# FPGA_Supply.net
KiCad netlist of a schematic drawn in Altium Designer
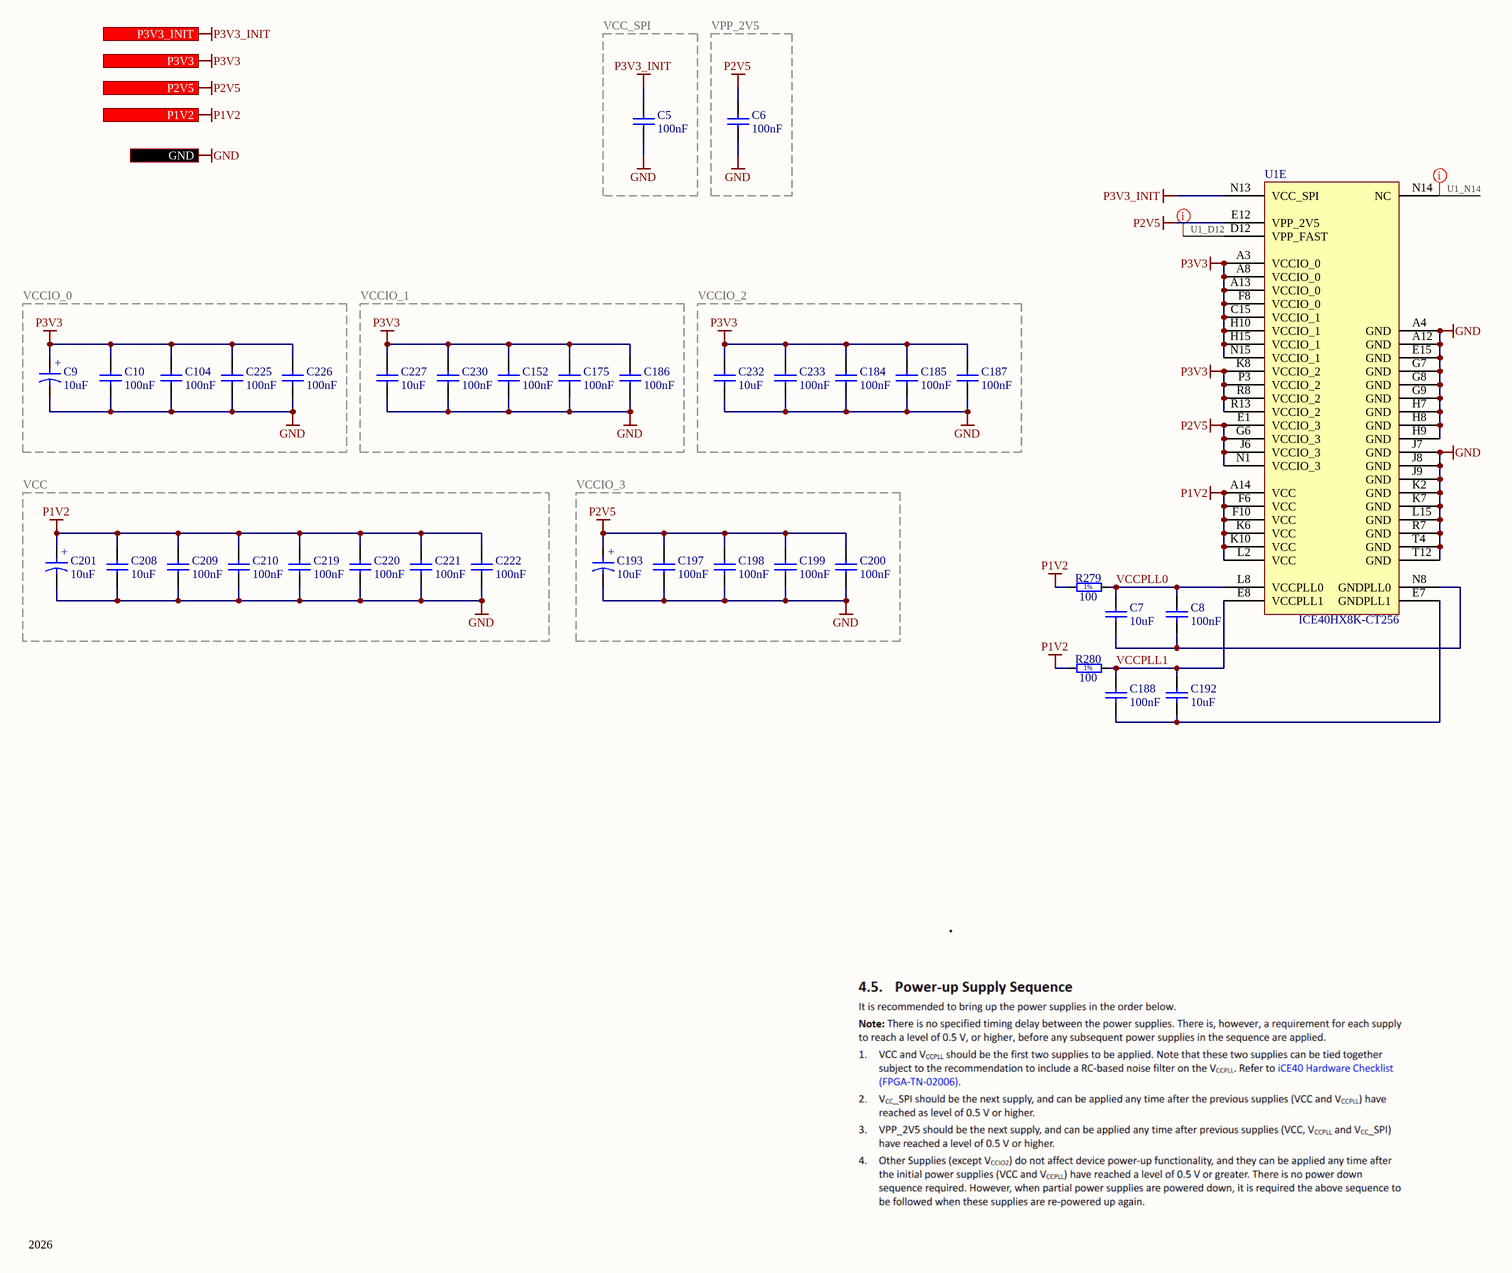
[diagram p0: FPGA_Supply.SchDoc]

(export (version "E")
  (design (tool "Eeschema 10.0.6"))
  (components
    (comp (ref "C5")
      (value "100nF")
      (footprint "CAPC1005X55N")
      (description "Non-polarised capacitor")
      (fields
        (field (name "PART NUMBER") "CC0402_100NF_16V_10%_X5R")
        (field (name "VOLTAGE") "16V")
        (field (name "AUTHOR") "CERN DEM JLC")
      )
      (libsource (lib "Capacitors") (part "Capacitor - non polarized"))
    )
    (comp (ref "C6")
      (value "100nF")
      (footprint "CAPC1005X55N")
      (description "Non-polarised capacitor")
      (fields
        (field (name "PART NUMBER") "CC0402_100NF_16V_10%_X5R")
        (field (name "VOLTAGE") "16V")
        (field (name "AUTHOR") "CERN DEM JLC")
      )
      (libsource (lib "Capacitors") (part "Capacitor - non polarized"))
    )
    (comp (ref "C7")
      (value "10uF")
      (footprint "CAPC1005X70N")
      (description "Non-polarised capacitor")
      (fields
        (field (name "PART NUMBER") "CC0402_10UF_6.3V_20%_X5R")
        (field (name "VOLTAGE") "6.3V")
        (field (name "AUTHOR") "CERN DEM JLC")
      )
      (libsource (lib "Capacitors") (part "Capacitor - non polarized"))
    )
    (comp (ref "C8")
      (value "100nF")
      (footprint "CAPC1005X55N")
      (description "Non-polarised capacitor")
      (fields
        (field (name "PART NUMBER") "CC0402_100NF_16V_10%_X5R")
        (field (name "VOLTAGE") "16V")
        (field (name "AUTHOR") "CERN DEM JLC")
      )
      (libsource (lib "Capacitors") (part "Capacitor - non polarized"))
    )
    (comp (ref "C9")
      (value "10uF")
      (footprint "CAPMP3216X180N")
      (description "Polarised capacitor")
      (fields
        (field (name "PART NUMBER") "CTE3216-18_10UF_16V_20%_AVX_TCJ")
        (field (name "VOLTAGE") "16V")
        (field (name "AUTHOR") "CERN DEM JLC")
      )
      (libsource (lib "Capacitors") (part "Capacitor - polarized"))
    )
    (comp (ref "C10")
      (value "100nF")
      (footprint "CAPC1005X55N")
      (description "Non-polarised capacitor")
      (fields
        (field (name "PART NUMBER") "CC0402_100NF_16V_10%_X5R")
        (field (name "VOLTAGE") "16V")
        (field (name "AUTHOR") "CERN DEM JLC")
      )
      (libsource (lib "Capacitors") (part "Capacitor - non polarized"))
    )
    (comp (ref "C104")
      (value "100nF")
      (footprint "CAPC1005X55N")
      (description "Non-polarised capacitor")
      (fields
        (field (name "PART NUMBER") "CC0402_100NF_16V_10%_X5R")
        (field (name "VOLTAGE") "16V")
        (field (name "AUTHOR") "CERN DEM JLC")
      )
      (libsource (lib "Capacitors") (part "Capacitor - non polarized"))
    )
    (comp (ref "C152")
      (value "100nF")
      (footprint "CAPC1005X55N")
      (description "Non-polarised capacitor")
      (fields
        (field (name "PART NUMBER") "CC0402_100NF_16V_10%_X5R")
        (field (name "VOLTAGE") "16V")
        (field (name "AUTHOR") "CERN DEM JLC")
      )
      (libsource (lib "Capacitors") (part "Capacitor - non polarized"))
    )
    (comp (ref "C175")
      (value "100nF")
      (footprint "CAPC1005X55N")
      (description "Non-polarised capacitor")
      (fields
        (field (name "PART NUMBER") "CC0402_100NF_16V_10%_X5R")
        (field (name "VOLTAGE") "16V")
        (field (name "AUTHOR") "CERN DEM JLC")
      )
      (libsource (lib "Capacitors") (part "Capacitor - non polarized"))
    )
    (comp (ref "C184")
      (value "100nF")
      (footprint "CAPC1005X55N")
      (description "Non-polarised capacitor")
      (fields
        (field (name "PART NUMBER") "CC0402_100NF_16V_10%_X5R")
        (field (name "VOLTAGE") "16V")
        (field (name "AUTHOR") "CERN DEM JLC")
      )
      (libsource (lib "Capacitors") (part "Capacitor - non polarized"))
    )
    (comp (ref "C185")
      (value "100nF")
      (footprint "CAPC1005X55N")
      (description "Non-polarised capacitor")
      (fields
        (field (name "PART NUMBER") "CC0402_100NF_16V_10%_X5R")
        (field (name "VOLTAGE") "16V")
        (field (name "AUTHOR") "CERN DEM JLC")
      )
      (libsource (lib "Capacitors") (part "Capacitor - non polarized"))
    )
    (comp (ref "C186")
      (value "100nF")
      (footprint "CAPC1005X55N")
      (description "Non-polarised capacitor")
      (fields
        (field (name "PART NUMBER") "CC0402_100NF_16V_10%_X5R")
        (field (name "VOLTAGE") "16V")
        (field (name "AUTHOR") "CERN DEM JLC")
      )
      (libsource (lib "Capacitors") (part "Capacitor - non polarized"))
    )
    (comp (ref "C187")
      (value "100nF")
      (footprint "CAPC1005X55N")
      (description "Non-polarised capacitor")
      (fields
        (field (name "PART NUMBER") "CC0402_100NF_16V_10%_X5R")
        (field (name "VOLTAGE") "16V")
        (field (name "AUTHOR") "CERN DEM JLC")
      )
      (libsource (lib "Capacitors") (part "Capacitor - non polarized"))
    )
    (comp (ref "C188")
      (value "100nF")
      (footprint "CAPC1005X55N")
      (description "Non-polarised capacitor")
      (fields
        (field (name "PART NUMBER") "CC0402_100NF_16V_10%_X5R")
        (field (name "VOLTAGE") "16V")
        (field (name "AUTHOR") "CERN DEM JLC")
      )
      (libsource (lib "Capacitors") (part "Capacitor - non polarized"))
    )
    (comp (ref "C192")
      (value "10uF")
      (footprint "CAPC1005X70N")
      (description "Non-polarised capacitor")
      (fields
        (field (name "PART NUMBER") "CC0402_10UF_6.3V_20%_X5R")
        (field (name "VOLTAGE") "6.3V")
        (field (name "AUTHOR") "CERN DEM JLC")
      )
      (libsource (lib "Capacitors") (part "Capacitor - non polarized"))
    )
    (comp (ref "C193")
      (value "10uF")
      (footprint "CAPMP3216X180N")
      (description "Polarised capacitor")
      (fields
        (field (name "PART NUMBER") "CTE3216-18_10UF_16V_20%_AVX_TCJ")
        (field (name "VOLTAGE") "16V")
        (field (name "AUTHOR") "CERN DEM JLC")
      )
      (libsource (lib "Capacitors") (part "Capacitor - polarized"))
    )
    (comp (ref "C197")
      (value "100nF")
      (footprint "CAPC1005X55N")
      (description "Non-polarised capacitor")
      (fields
        (field (name "PART NUMBER") "CC0402_100NF_16V_10%_X5R")
        (field (name "VOLTAGE") "16V")
        (field (name "AUTHOR") "CERN DEM JLC")
      )
      (libsource (lib "Capacitors") (part "Capacitor - non polarized"))
    )
    (comp (ref "C198")
      (value "100nF")
      (footprint "CAPC1005X55N")
      (description "Non-polarised capacitor")
      (fields
        (field (name "PART NUMBER") "CC0402_100NF_16V_10%_X5R")
        (field (name "VOLTAGE") "16V")
        (field (name "AUTHOR") "CERN DEM JLC")
      )
      (libsource (lib "Capacitors") (part "Capacitor - non polarized"))
    )
    (comp (ref "C199")
      (value "100nF")
      (footprint "CAPC1005X55N")
      (description "Non-polarised capacitor")
      (fields
        (field (name "PART NUMBER") "CC0402_100NF_16V_10%_X5R")
        (field (name "VOLTAGE") "16V")
        (field (name "AUTHOR") "CERN DEM JLC")
      )
      (libsource (lib "Capacitors") (part "Capacitor - non polarized"))
    )
    (comp (ref "C200")
      (value "100nF")
      (footprint "CAPC1005X55N")
      (description "Non-polarised capacitor")
      (fields
        (field (name "PART NUMBER") "CC0402_100NF_16V_10%_X5R")
        (field (name "VOLTAGE") "16V")
        (field (name "AUTHOR") "CERN DEM JLC")
      )
      (libsource (lib "Capacitors") (part "Capacitor - non polarized"))
    )
    (comp (ref "C201")
      (value "10uF")
      (footprint "CAPMP3216X180N")
      (description "Polarised capacitor")
      (fields
        (field (name "PART NUMBER") "CTE3216-18_10UF_16V_20%_AVX_TCJ")
        (field (name "VOLTAGE") "16V")
        (field (name "AUTHOR") "CERN DEM JLC")
      )
      (libsource (lib "Capacitors") (part "Capacitor - polarized"))
    )
    (comp (ref "C208")
      (value "10uF")
      (footprint "CAPC2012X135N")
      (description "Non-polarised capacitor")
      (fields
        (field (name "PART NUMBER") "CC0805_10UF_16V_10%_X5R")
        (field (name "VOLTAGE") "16V")
        (field (name "AUTHOR") "CERN DEM JLC")
      )
      (libsource (lib "Capacitors") (part "Capacitor - non polarized"))
    )
    (comp (ref "C209")
      (value "100nF")
      (footprint "CAPC1005X55N")
      (description "Non-polarised capacitor")
      (fields
        (field (name "PART NUMBER") "CC0402_100NF_16V_10%_X5R")
        (field (name "VOLTAGE") "16V")
        (field (name "AUTHOR") "CERN DEM JLC")
      )
      (libsource (lib "Capacitors") (part "Capacitor - non polarized"))
    )
    (comp (ref "C210")
      (value "100nF")
      (footprint "CAPC1005X55N")
      (description "Non-polarised capacitor")
      (fields
        (field (name "PART NUMBER") "CC0402_100NF_16V_10%_X5R")
        (field (name "VOLTAGE") "16V")
        (field (name "AUTHOR") "CERN DEM JLC")
      )
      (libsource (lib "Capacitors") (part "Capacitor - non polarized"))
    )
    (comp (ref "C219")
      (value "100nF")
      (footprint "CAPC1005X55N")
      (description "Non-polarised capacitor")
      (fields
        (field (name "PART NUMBER") "CC0402_100NF_16V_10%_X5R")
        (field (name "VOLTAGE") "16V")
        (field (name "AUTHOR") "CERN DEM JLC")
      )
      (libsource (lib "Capacitors") (part "Capacitor - non polarized"))
    )
    (comp (ref "C220")
      (value "100nF")
      (footprint "CAPC1005X55N")
      (description "Non-polarised capacitor")
      (fields
        (field (name "PART NUMBER") "CC0402_100NF_16V_10%_X5R")
        (field (name "VOLTAGE") "16V")
        (field (name "AUTHOR") "CERN DEM JLC")
      )
      (libsource (lib "Capacitors") (part "Capacitor - non polarized"))
    )
    (comp (ref "C221")
      (value "100nF")
      (footprint "CAPC1005X55N")
      (description "Non-polarised capacitor")
      (fields
        (field (name "PART NUMBER") "CC0402_100NF_16V_10%_X5R")
        (field (name "VOLTAGE") "16V")
        (field (name "AUTHOR") "CERN DEM JLC")
      )
      (libsource (lib "Capacitors") (part "Capacitor - non polarized"))
    )
    (comp (ref "C222")
      (value "100nF")
      (footprint "CAPC1005X55N")
      (description "Non-polarised capacitor")
      (fields
        (field (name "PART NUMBER") "CC0402_100NF_16V_10%_X5R")
        (field (name "VOLTAGE") "16V")
        (field (name "AUTHOR") "CERN DEM JLC")
      )
      (libsource (lib "Capacitors") (part "Capacitor - non polarized"))
    )
    (comp (ref "C225")
      (value "100nF")
      (footprint "CAPC1005X55N")
      (description "Non-polarised capacitor")
      (fields
        (field (name "PART NUMBER") "CC0402_100NF_16V_10%_X5R")
        (field (name "VOLTAGE") "16V")
        (field (name "AUTHOR") "CERN DEM JLC")
      )
      (libsource (lib "Capacitors") (part "Capacitor - non polarized"))
    )
    (comp (ref "C226")
      (value "100nF")
      (footprint "CAPC1005X55N")
      (description "Non-polarised capacitor")
      (fields
        (field (name "PART NUMBER") "CC0402_100NF_16V_10%_X5R")
        (field (name "VOLTAGE") "16V")
        (field (name "AUTHOR") "CERN DEM JLC")
      )
      (libsource (lib "Capacitors") (part "Capacitor - non polarized"))
    )
    (comp (ref "C227")
      (value "10uF")
      (footprint "CAPC2012X135N")
      (description "Non-polarised capacitor")
      (fields
        (field (name "PART NUMBER") "CC0805_10UF_16V_10%_X5R")
        (field (name "VOLTAGE") "16V")
        (field (name "AUTHOR") "CERN DEM JLC")
      )
      (libsource (lib "Capacitors") (part "Capacitor - non polarized"))
    )
    (comp (ref "C230")
      (value "100nF")
      (footprint "CAPC1005X55N")
      (description "Non-polarised capacitor")
      (fields
        (field (name "PART NUMBER") "CC0402_100NF_16V_10%_X5R")
        (field (name "VOLTAGE") "16V")
        (field (name "AUTHOR") "CERN DEM JLC")
      )
      (libsource (lib "Capacitors") (part "Capacitor - non polarized"))
    )
    (comp (ref "C232")
      (value "10uF")
      (footprint "CAPC2012X135N")
      (description "Non-polarised capacitor")
      (fields
        (field (name "PART NUMBER") "CC0805_10UF_16V_10%_X5R")
        (field (name "VOLTAGE") "16V")
        (field (name "AUTHOR") "CERN DEM JLC")
      )
      (libsource (lib "Capacitors") (part "Capacitor - non polarized"))
    )
    (comp (ref "C233")
      (value "100nF")
      (footprint "CAPC1005X55N")
      (description "Non-polarised capacitor")
      (fields
        (field (name "PART NUMBER") "CC0402_100NF_16V_10%_X5R")
        (field (name "VOLTAGE") "16V")
        (field (name "AUTHOR") "CERN DEM JLC")
      )
      (libsource (lib "Capacitors") (part "Capacitor - non polarized"))
    )
    (comp (ref "R279")
      (value "100")
      (footprint "RESC1005X40N")
      (description "Resistor - 1%")
      (fields
        (field (name "PART NUMBER") "R0402_100R_1%_0.0625W_100PPM")
        (field (name "POWER") "0.0625W")
        (field (name "AUTHOR") "CERN DEM JLC")
      )
      (libsource (lib "Resistors") (part "Resistor - 1%"))
    )
    (comp (ref "R280")
      (value "100")
      (footprint "RESC1005X40N")
      (description "Resistor - 1%")
      (fields
        (field (name "PART NUMBER") "R0402_100R_1%_0.0625W_100PPM")
        (field (name "POWER") "0.0625W")
        (field (name "AUTHOR") "CERN DEM JLC")
      )
      (libsource (lib "Resistors") (part "Resistor - 1%"))
    )
    (comp (ref "U1")
      (value "ICE40HX8K-CT256")
      (footprint "LATC-caBGA-256")
      (fields (field (name "MANUFACTURER") "Lattice Semiconductor"))
      (libsource (lib "Altium Content Vault") (part "LATC-HX8K-caBGA-256"))
    )
  )
  (nets
    (net (code "1") (name "/U1_D12") (class "Default")
      (node (ref "U1") (pin "D12") (pinfunction "VPP_FAST_D12") (pintype "power_in"))
    )
    (net (code "2") (name "/U1_N14") (class "Default")
      (node (ref "U1") (pin "N14") (pinfunction "NC_N14") (pintype "passive"))
    )
    (net (code "3") (name "/VCCPLL0") (class "Default")
      (node (ref "C7") (pin "2") (pinfunction "2_2") (pintype "passive"))
      (node (ref "C8") (pin "2") (pinfunction "2_2") (pintype "passive"))
      (node (ref "R279") (pin "2") (pinfunction "2_2") (pintype "passive"))
      (node (ref "U1") (pin "L8") (pinfunction "VCCPLL0_L8") (pintype "power_in"))
    )
    (net (code "4") (name "/VCCPLL1") (class "Default")
      (node (ref "C188") (pin "2") (pinfunction "2_2") (pintype "passive"))
      (node (ref "C192") (pin "2") (pinfunction "2_2") (pintype "passive"))
      (node (ref "R280") (pin "2") (pinfunction "2_2") (pintype "passive"))
      (node (ref "U1") (pin "E8") (pinfunction "VCCPLL1_E8") (pintype "power_in"))
    )
    (net (code "5") (name "GND") (class "Default")
      (node (ref "C10") (pin "1") (pinfunction "1_1") (pintype "passive"))
      (node (ref "C104") (pin "1") (pinfunction "1_1") (pintype "passive"))
      (node (ref "C152") (pin "1") (pinfunction "1_1") (pintype "passive"))
      (node (ref "C175") (pin "1") (pinfunction "1_1") (pintype "passive"))
      (node (ref "C184") (pin "1") (pinfunction "1_1") (pintype "passive"))
      (node (ref "C185") (pin "1") (pinfunction "1_1") (pintype "passive"))
      (node (ref "C186") (pin "1") (pinfunction "1_1") (pintype "passive"))
      (node (ref "C187") (pin "1") (pinfunction "1_1") (pintype "passive"))
      (node (ref "C193") (pin "2") (pinfunction "2_2") (pintype "passive"))
      (node (ref "C197") (pin "1") (pinfunction "1_1") (pintype "passive"))
      (node (ref "C198") (pin "1") (pinfunction "1_1") (pintype "passive"))
      (node (ref "C199") (pin "1") (pinfunction "1_1") (pintype "passive"))
      (node (ref "C200") (pin "1") (pinfunction "1_1") (pintype "passive"))
      (node (ref "C201") (pin "2") (pinfunction "2_2") (pintype "passive"))
      (node (ref "C208") (pin "1") (pinfunction "1_1") (pintype "passive"))
      (node (ref "C209") (pin "1") (pinfunction "1_1") (pintype "passive"))
      (node (ref "C210") (pin "1") (pinfunction "1_1") (pintype "passive"))
      (node (ref "C219") (pin "1") (pinfunction "1_1") (pintype "passive"))
      (node (ref "C220") (pin "1") (pinfunction "1_1") (pintype "passive"))
      (node (ref "C221") (pin "1") (pinfunction "1_1") (pintype "passive"))
      (node (ref "C222") (pin "1") (pinfunction "1_1") (pintype "passive"))
      (node (ref "C225") (pin "1") (pinfunction "1_1") (pintype "passive"))
      (node (ref "C226") (pin "1") (pinfunction "1_1") (pintype "passive"))
      (node (ref "C227") (pin "1") (pinfunction "1_1") (pintype "passive"))
      (node (ref "C230") (pin "1") (pinfunction "1_1") (pintype "passive"))
      (node (ref "C232") (pin "1") (pinfunction "1_1") (pintype "passive"))
      (node (ref "C233") (pin "1") (pinfunction "1_1") (pintype "passive"))
      (node (ref "C5") (pin "1") (pinfunction "1_1") (pintype "passive"))
      (node (ref "C6") (pin "1") (pinfunction "1_1") (pintype "passive"))
      (node (ref "C9") (pin "2") (pinfunction "2_2") (pintype "passive"))
      (node (ref "U1") (pin "A12") (pinfunction "GND_A12") (pintype "power_in"))
      (node (ref "U1") (pin "A4") (pinfunction "GND_A4") (pintype "power_in"))
      (node (ref "U1") (pin "E15") (pinfunction "GND_E15") (pintype "power_in"))
      (node (ref "U1") (pin "G7") (pinfunction "GND_G7") (pintype "power_in"))
      (node (ref "U1") (pin "G8") (pinfunction "GND_G8") (pintype "power_in"))
      (node (ref "U1") (pin "G9") (pinfunction "GND_G9") (pintype "power_in"))
      (node (ref "U1") (pin "H7") (pinfunction "GND_H7") (pintype "power_in"))
      (node (ref "U1") (pin "H8") (pinfunction "GND_H8") (pintype "power_in"))
      (node (ref "U1") (pin "H9") (pinfunction "GND_H9") (pintype "power_in"))
      (node (ref "U1") (pin "J7") (pinfunction "GND_J7") (pintype "power_in"))
      (node (ref "U1") (pin "J8") (pinfunction "GND_J8") (pintype "power_in"))
      (node (ref "U1") (pin "J9") (pinfunction "GND_J9") (pintype "power_in"))
      (node (ref "U1") (pin "K2") (pinfunction "GND_K2") (pintype "power_in"))
      (node (ref "U1") (pin "K7") (pinfunction "GND_K7") (pintype "power_in"))
      (node (ref "U1") (pin "L15") (pinfunction "GND_L15") (pintype "power_in"))
      (node (ref "U1") (pin "R7") (pinfunction "GND_R7") (pintype "power_in"))
      (node (ref "U1") (pin "T12") (pinfunction "GND_T12") (pintype "power_in"))
      (node (ref "U1") (pin "T4") (pinfunction "GND_T4") (pintype "power_in"))
    )
    (net (code "6") (name "Net-(U1E-GNDPLL0)") (class "Default")
      (node (ref "C7") (pin "1") (pinfunction "1_1") (pintype "passive"))
      (node (ref "C8") (pin "1") (pinfunction "1_1") (pintype "passive"))
      (node (ref "U1") (pin "N8") (pinfunction "GNDPLL0_N8") (pintype "power_in"))
    )
    (net (code "7") (name "Net-(U1E-GNDPLL1)") (class "Default")
      (node (ref "C188") (pin "1") (pinfunction "1_1") (pintype "passive"))
      (node (ref "C192") (pin "1") (pinfunction "1_1") (pintype "passive"))
      (node (ref "U1") (pin "E7") (pinfunction "GNDPLL1_E7") (pintype "power_in"))
    )
    (net (code "8") (name "P1V2") (class "Default")
      (node (ref "C201") (pin "1") (pinfunction "1_1") (pintype "passive"))
      (node (ref "C208") (pin "2") (pinfunction "2_2") (pintype "passive"))
      (node (ref "C209") (pin "2") (pinfunction "2_2") (pintype "passive"))
      (node (ref "C210") (pin "2") (pinfunction "2_2") (pintype "passive"))
      (node (ref "C219") (pin "2") (pinfunction "2_2") (pintype "passive"))
      (node (ref "C220") (pin "2") (pinfunction "2_2") (pintype "passive"))
      (node (ref "C221") (pin "2") (pinfunction "2_2") (pintype "passive"))
      (node (ref "C222") (pin "2") (pinfunction "2_2") (pintype "passive"))
      (node (ref "R279") (pin "1") (pinfunction "1_1") (pintype "passive"))
      (node (ref "R280") (pin "1") (pinfunction "1_1") (pintype "passive"))
      (node (ref "U1") (pin "A14") (pinfunction "VCC_A14") (pintype "power_in"))
      (node (ref "U1") (pin "F10") (pinfunction "VCC_F10") (pintype "power_in"))
      (node (ref "U1") (pin "F6") (pinfunction "VCC_F6") (pintype "power_in"))
      (node (ref "U1") (pin "K10") (pinfunction "VCC_K10") (pintype "power_in"))
      (node (ref "U1") (pin "K6") (pinfunction "VCC_K6") (pintype "power_in"))
      (node (ref "U1") (pin "L2") (pinfunction "VCC_L2") (pintype "power_in"))
    )
    (net (code "9") (name "P2V5") (class "Default")
      (node (ref "C193") (pin "1") (pinfunction "1_1") (pintype "passive"))
      (node (ref "C197") (pin "2") (pinfunction "2_2") (pintype "passive"))
      (node (ref "C198") (pin "2") (pinfunction "2_2") (pintype "passive"))
      (node (ref "C199") (pin "2") (pinfunction "2_2") (pintype "passive"))
      (node (ref "C200") (pin "2") (pinfunction "2_2") (pintype "passive"))
      (node (ref "C6") (pin "2") (pinfunction "2_2") (pintype "passive"))
      (node (ref "U1") (pin "E1") (pinfunction "VCCIO_3_E1") (pintype "power_in"))
      (node (ref "U1") (pin "E12") (pinfunction "VPP_2V5_E12") (pintype "power_in"))
      (node (ref "U1") (pin "G6") (pinfunction "VCCIO_3_G6") (pintype "power_in"))
      (node (ref "U1") (pin "J6") (pinfunction "VCCIO_3_J6") (pintype "power_in"))
      (node (ref "U1") (pin "N1") (pinfunction "VCCIO_3_N1") (pintype "power_in"))
    )
    (net (code "10") (name "P3V3") (class "Default")
      (node (ref "C10") (pin "2") (pinfunction "2_2") (pintype "passive"))
      (node (ref "C104") (pin "2") (pinfunction "2_2") (pintype "passive"))
      (node (ref "C152") (pin "2") (pinfunction "2_2") (pintype "passive"))
      (node (ref "C175") (pin "2") (pinfunction "2_2") (pintype "passive"))
      (node (ref "C184") (pin "2") (pinfunction "2_2") (pintype "passive"))
      (node (ref "C185") (pin "2") (pinfunction "2_2") (pintype "passive"))
      (node (ref "C186") (pin "2") (pinfunction "2_2") (pintype "passive"))
      (node (ref "C187") (pin "2") (pinfunction "2_2") (pintype "passive"))
      (node (ref "C225") (pin "2") (pinfunction "2_2") (pintype "passive"))
      (node (ref "C226") (pin "2") (pinfunction "2_2") (pintype "passive"))
      (node (ref "C227") (pin "2") (pinfunction "2_2") (pintype "passive"))
      (node (ref "C230") (pin "2") (pinfunction "2_2") (pintype "passive"))
      (node (ref "C232") (pin "2") (pinfunction "2_2") (pintype "passive"))
      (node (ref "C233") (pin "2") (pinfunction "2_2") (pintype "passive"))
      (node (ref "C9") (pin "1") (pinfunction "1_1") (pintype "passive"))
      (node (ref "U1") (pin "A13") (pinfunction "VCCIO_0_A13") (pintype "power_in"))
      (node (ref "U1") (pin "A3") (pinfunction "VCCIO_0_A3") (pintype "power_in"))
      (node (ref "U1") (pin "A8") (pinfunction "VCCIO_0_A8") (pintype "power_in"))
      (node (ref "U1") (pin "C15") (pinfunction "VCCIO_1_C15") (pintype "power_in"))
      (node (ref "U1") (pin "F8") (pinfunction "VCCIO_0_F8") (pintype "power_in"))
      (node (ref "U1") (pin "H10") (pinfunction "VCCIO_1_H10") (pintype "power_in"))
      (node (ref "U1") (pin "H15") (pinfunction "VCCIO_1_H15") (pintype "power_in"))
      (node (ref "U1") (pin "K8") (pinfunction "VCCIO_2_K8") (pintype "power_in"))
      (node (ref "U1") (pin "N15") (pinfunction "VCCIO_1_N15") (pintype "power_in"))
      (node (ref "U1") (pin "P3") (pinfunction "VCCIO_2_P3") (pintype "power_in"))
      (node (ref "U1") (pin "R13") (pinfunction "VCCIO_2_R13") (pintype "power_in"))
      (node (ref "U1") (pin "R8") (pinfunction "VCCIO_2_R8") (pintype "power_in"))
    )
    (net (code "11") (name "P3V3_INIT") (class "Default")
      (node (ref "C5") (pin "2") (pinfunction "2_2") (pintype "passive"))
      (node (ref "U1") (pin "N13") (pinfunction "VCC_SPI_N13") (pintype "power_in"))
    )
  )
)
